# blaster.net
KiCad netlist of a schematic drawn in EAGLE
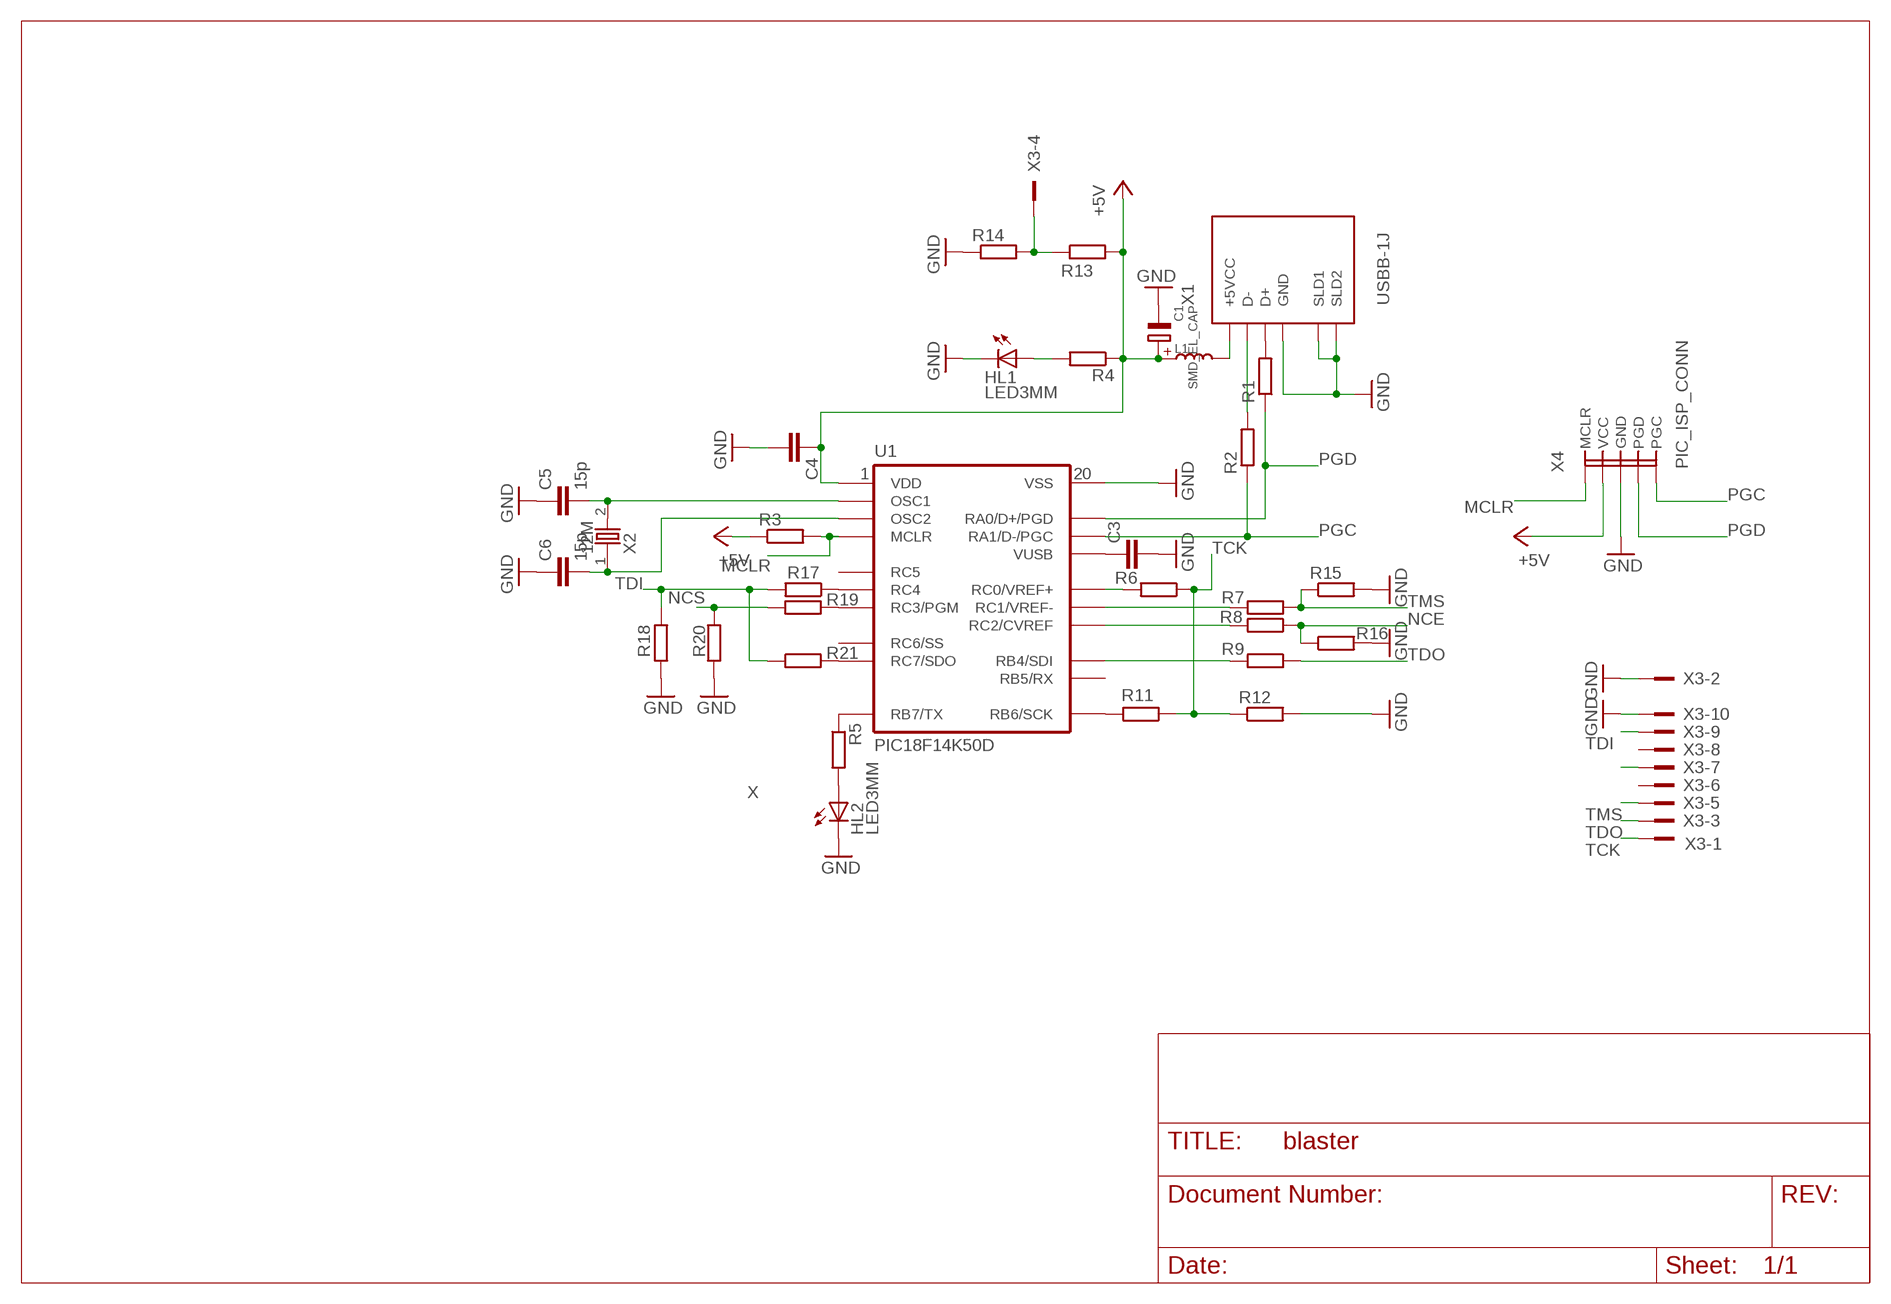
[diagram p0: schematic, sheet 1]

(export (version "E")
  (design (tool "Eeschema 10.0.6"))
  (components
    (comp (ref "C1")
      (value "SMD_EL_CAP")
      (footprint "eagle-import:153CLV-0405")
      (libsource (lib "eagle-import") (part "SMD_EL_CAP"))
    )
    (comp (ref "C3")
      (value "SMD_CAPC1206K")
      (footprint "eagle-import:C1206K")
      (libsource (lib "eagle-import") (part "SMD_CAPC1206K"))
    )
    (comp (ref "C4")
      (value "SMD_CAPC1206K")
      (footprint "eagle-import:C1206K")
      (libsource (lib "eagle-import") (part "SMD_CAPC1206K"))
    )
    (comp (ref "C5")
      (value "15p")
      (footprint "eagle-import:C0805D")
      (libsource (lib "eagle-import") (part "C0805"))
    )
    (comp (ref "C6")
      (value "15p")
      (footprint "eagle-import:C0805D")
      (libsource (lib "eagle-import") (part "C0805"))
    )
    (comp (ref "HL1")
      (value "LED3MM")
      (footprint "eagle-import:LED3MM")
      (libsource (lib "eagle-import") (part "LED3MM"))
    )
    (comp (ref "HL2")
      (value "LED3MM")
      (footprint "eagle-import:LED3MM")
      (libsource (lib "eagle-import") (part "LED3MM"))
    )
    (comp (ref "L1")
      (value "INDUCTORIND2")
      (footprint "eagle-import:INDUCTOR2")
      (libsource (lib "eagle-import") (part "INDUCTORIND2"))
    )
    (comp (ref "R1")
      (value "SMD_RES")
      (footprint "eagle-import:R1206")
      (libsource (lib "eagle-import") (part "SMD_RES"))
    )
    (comp (ref "R2")
      (value "SMD_RES")
      (footprint "eagle-import:R1206")
      (libsource (lib "eagle-import") (part "SMD_RES"))
    )
    (comp (ref "R3")
      (value "10k")
      (footprint "eagle-import:R1206")
      (libsource (lib "eagle-import") (part "SMD_RES"))
    )
    (comp (ref "R4")
      (value "1k")
      (footprint "eagle-import:R1206")
      (libsource (lib "eagle-import") (part "SMD_RES"))
    )
    (comp (ref "R5")
      (value "1k")
      (footprint "eagle-import:R1206")
      (libsource (lib "eagle-import") (part "SMD_RES"))
    )
    (comp (ref "R6")
      (value "100")
      (footprint "eagle-import:R1206")
      (libsource (lib "eagle-import") (part "SMD_RES"))
    )
    (comp (ref "R7")
      (value "100")
      (footprint "eagle-import:R1206")
      (libsource (lib "eagle-import") (part "SMD_RES"))
    )
    (comp (ref "R8")
      (value "100")
      (footprint "eagle-import:R1206")
      (libsource (lib "eagle-import") (part "SMD_RES"))
    )
    (comp (ref "R9")
      (value "100")
      (footprint "eagle-import:R1206")
      (libsource (lib "eagle-import") (part "SMD_RES"))
    )
    (comp (ref "R11")
      (value "100")
      (footprint "eagle-import:R1206")
      (libsource (lib "eagle-import") (part "SMD_RES"))
    )
    (comp (ref "R12")
      (value "200")
      (footprint "eagle-import:R1206")
      (libsource (lib "eagle-import") (part "SMD_RES"))
    )
    (comp (ref "R13")
      (value "100")
      (footprint "eagle-import:R1206")
      (libsource (lib "eagle-import") (part "SMD_RES"))
    )
    (comp (ref "R14")
      (value "200")
      (footprint "eagle-import:R1206")
      (libsource (lib "eagle-import") (part "SMD_RES"))
    )
    (comp (ref "R15")
      (value "200")
      (footprint "eagle-import:R1206")
      (libsource (lib "eagle-import") (part "SMD_RES"))
    )
    (comp (ref "R16")
      (value "200")
      (footprint "eagle-import:R1206")
      (libsource (lib "eagle-import") (part "SMD_RES"))
    )
    (comp (ref "R17")
      (value "100")
      (footprint "eagle-import:R1206")
      (libsource (lib "eagle-import") (part "SMD_RES"))
    )
    (comp (ref "R18")
      (value "200")
      (footprint "eagle-import:R1206")
      (libsource (lib "eagle-import") (part "SMD_RES"))
    )
    (comp (ref "R19")
      (value "100")
      (footprint "eagle-import:R1206")
      (libsource (lib "eagle-import") (part "SMD_RES"))
    )
    (comp (ref "R20")
      (value "200")
      (footprint "eagle-import:R1206")
      (libsource (lib "eagle-import") (part "SMD_RES"))
    )
    (comp (ref "R21")
      (value "100")
      (footprint "eagle-import:R1206")
      (libsource (lib "eagle-import") (part "SMD_RES"))
    )
    (comp (ref "U1")
      (value "PIC18F14K50D")
      (footprint "eagle-import:SO20-DW")
      (libsource (lib "eagle-import") (part "PIC18F14K50D"))
    )
    (comp (ref "X1")
      (value "USBB-1J")
      (footprint "eagle-import:USBB-1J")
      (libsource (lib "eagle-import") (part "USBB-1J"))
    )
    (comp (ref "X2")
      (value "12М")
      (footprint "eagle-import:HC49_S")
      (libsource (lib "eagle-import") (part "HC49/S"))
    )
    (comp (ref "X3")
      (value "X")
      (footprint "eagle-import:PAK100_2500-5-10")
      (fields (field (name "OC_FARNELL") "1788669") (field (name "OC_NEWARK") "unknown"))
      (libsource (lib "eagle-import") (part "DC-10_CON5"))
    )
    (comp (ref "X4")
      (value "PIC_ISP_CONN")
      (footprint "eagle-import:PLC-5PIN")
      (libsource (lib "eagle-import") (part "PIC_ISP_CONN"))
    )
  )
  (nets
    (net (code "1") (name "+5V") (class "Default")
      (node (ref "C1") (pin "+") (pinfunction "P$1_+") (pintype "bidirectional"))
      (node (ref "C4") (pin "1") (pinfunction "1_1") (pintype "passive"))
      (node (ref "L1") (pin "P$1") (pinfunction "P$1_P$1") (pintype "bidirectional"))
      (node (ref "R13") (pin "2") (pinfunction "2_2") (pintype "passive"))
      (node (ref "R3") (pin "1") (pinfunction "1_1") (pintype "passive"))
      (node (ref "R4") (pin "1") (pinfunction "1_1") (pintype "passive"))
      (node (ref "U1") (pin "1.1") (pinfunction "VDD_1.1") (pintype "power_in"))
      (node (ref "X4") (pin "P$2") (pinfunction "VCC_P$2") (pintype "bidirectional"))
    )
    (net (code "2") (name "/MCLR") (class "Default")
      (node (ref "R3") (pin "2") (pinfunction "2_2") (pintype "passive"))
      (node (ref "U1") (pin "1.4") (pinfunction "MCLR_1.4") (pintype "passive"))
      (node (ref "X4") (pin "P$1") (pinfunction "MCLR_P$1") (pintype "bidirectional"))
    )
    (net (code "3") (name "/NCE") (class "Default")
      (node (ref "R16") (pin "1") (pinfunction "1_1") (pintype "passive"))
      (node (ref "R8") (pin "1") (pinfunction "1_1") (pintype "passive"))
    )
    (net (code "4") (name "/NCS") (class "Default")
      (node (ref "R19") (pin "1") (pinfunction "1_1") (pintype "passive"))
      (node (ref "R20") (pin "2") (pinfunction "2_2") (pintype "passive"))
    )
    (net (code "5") (name "/PGC") (class "Default")
      (node (ref "R2") (pin "1") (pinfunction "1_1") (pintype "passive"))
      (node (ref "U1") (pin "1.18") (pinfunction "RA1/D-/PGC_1.18") (pintype "power_in"))
      (node (ref "X4") (pin "P$5") (pinfunction "PGC_P$5") (pintype "bidirectional"))
    )
    (net (code "6") (name "/PGD") (class "Default")
      (node (ref "R1") (pin "1") (pinfunction "1_1") (pintype "passive"))
      (node (ref "U1") (pin "1.19") (pinfunction "RA0/D+/PGD_1.19") (pintype "power_in"))
      (node (ref "X4") (pin "P$4") (pinfunction "PGD_P$4") (pintype "bidirectional"))
    )
    (net (code "7") (name "/TCK") (class "Default")
      (node (ref "R11") (pin "1") (pinfunction "1_1") (pintype "passive"))
      (node (ref "R12") (pin "1") (pinfunction "1_1") (pintype "passive"))
      (node (ref "R6") (pin "1") (pinfunction "1_1") (pintype "passive"))
      (node (ref "X3") (pin "1") (pinfunction "KL_1") (pintype "passive"))
    )
    (net (code "8") (name "/TDI") (class "Default")
      (node (ref "R17") (pin "2") (pinfunction "2_2") (pintype "passive"))
      (node (ref "R18") (pin "2") (pinfunction "2_2") (pintype "passive"))
      (node (ref "R21") (pin "1") (pinfunction "1_1") (pintype "passive"))
      (node (ref "X3") (pin "9") (pinfunction "KL_9") (pintype "passive"))
    )
    (net (code "9") (name "/TDO") (class "Default")
      (node (ref "R9") (pin "1") (pinfunction "1_1") (pintype "passive"))
      (node (ref "X3") (pin "3") (pinfunction "KL_3") (pintype "passive"))
    )
    (net (code "10") (name "/TMS") (class "Default")
      (node (ref "R15") (pin "1") (pinfunction "1_1") (pintype "passive"))
      (node (ref "R7") (pin "1") (pinfunction "1_1") (pintype "passive"))
      (node (ref "X3") (pin "5") (pinfunction "KL_5") (pintype "passive"))
    )
    (net (code "11") (name "GND") (class "Default")
      (node (ref "C1") (pin "-") (pinfunction "P$2_-") (pintype "bidirectional"))
      (node (ref "C3") (pin "2") (pinfunction "2_2") (pintype "passive"))
      (node (ref "C4") (pin "2") (pinfunction "2_2") (pintype "passive"))
      (node (ref "C5") (pin "1") (pinfunction "1_1") (pintype "passive"))
      (node (ref "C6") (pin "1") (pinfunction "1_1") (pintype "passive"))
      (node (ref "HL1") (pin "K") (pinfunction "C_K") (pintype "passive"))
      (node (ref "HL2") (pin "K") (pinfunction "C_K") (pintype "passive"))
      (node (ref "R12") (pin "2") (pinfunction "2_2") (pintype "passive"))
      (node (ref "R14") (pin "1") (pinfunction "1_1") (pintype "passive"))
      (node (ref "R15") (pin "2") (pinfunction "2_2") (pintype "passive"))
      (node (ref "R16") (pin "2") (pinfunction "2_2") (pintype "passive"))
      (node (ref "R18") (pin "1") (pinfunction "1_1") (pintype "passive"))
      (node (ref "R20") (pin "1") (pinfunction "1_1") (pintype "passive"))
      (node (ref "U1") (pin "1.20") (pinfunction "VSS_1.20") (pintype "power_in"))
      (node (ref "X1") (pin "4") (pinfunction "GND_4") (pintype "bidirectional"))
      (node (ref "X1") (pin "5") (pinfunction "SLD1_5") (pintype "bidirectional"))
      (node (ref "X1") (pin "6") (pinfunction "SLD2_6") (pintype "bidirectional"))
      (node (ref "X3") (pin "10") (pinfunction "KL_10") (pintype "passive"))
      (node (ref "X3") (pin "2") (pinfunction "KL_2") (pintype "passive"))
      (node (ref "X4") (pin "P$3") (pinfunction "GND_P$3") (pintype "bidirectional"))
    )
    (net (code "12") (name "Net-(HL1-PadA)") (class "Default")
      (node (ref "HL1") (pin "A") (pinfunction "A_A") (pintype "passive"))
      (node (ref "R4") (pin "2") (pinfunction "2_2") (pintype "passive"))
    )
    (net (code "13") (name "Net-(HL2-PadA)") (class "Default")
      (node (ref "HL2") (pin "A") (pinfunction "A_A") (pintype "passive"))
      (node (ref "R5") (pin "2") (pinfunction "2_2") (pintype "passive"))
    )
    (net (code "14") (name "Net-(U1-OSC1)") (class "Default")
      (node (ref "C5") (pin "2") (pinfunction "2_2") (pintype "passive"))
      (node (ref "U1") (pin "1.2") (pinfunction "OSC1_1.2") (pintype "power_in"))
      (node (ref "X2") (pin "2") (pinfunction "2_2") (pintype "passive"))
    )
    (net (code "15") (name "Net-(U1-OSC2)") (class "Default")
      (node (ref "C6") (pin "2") (pinfunction "2_2") (pintype "passive"))
      (node (ref "U1") (pin "1.3") (pinfunction "OSC2_1.3") (pintype "passive"))
      (node (ref "X2") (pin "1") (pinfunction "1_1") (pintype "passive"))
    )
    (net (code "16") (name "Net-(U1-RB4{slash}SDI)") (class "Default")
      (node (ref "R9") (pin "2") (pinfunction "2_2") (pintype "passive"))
      (node (ref "U1") (pin "1.13") (pinfunction "RB4/SDI_1.13") (pintype "output"))
    )
    (net (code "17") (name "Net-(U1-RB6{slash}SCK)") (class "Default")
      (node (ref "R11") (pin "2") (pinfunction "2_2") (pintype "passive"))
      (node (ref "U1") (pin "1.11") (pinfunction "RB6/SCK_1.11") (pintype "power_in"))
    )
    (net (code "18") (name "Net-(U1-RB7{slash}TX)") (class "Default")
      (node (ref "R5") (pin "1") (pinfunction "1_1") (pintype "passive"))
      (node (ref "U1") (pin "1.10") (pinfunction "RB7/TX_1.10") (pintype "bidirectional"))
    )
    (net (code "19") (name "Net-(U1-RC0{slash}VREF+)") (class "Default")
      (node (ref "R6") (pin "2") (pinfunction "2_2") (pintype "passive"))
      (node (ref "U1") (pin "1.16") (pinfunction "RC0/VREF+_1.16") (pintype "output"))
    )
    (net (code "20") (name "Net-(U1-RC1{slash}VREF-)") (class "Default")
      (node (ref "R7") (pin "2") (pinfunction "2_2") (pintype "passive"))
      (node (ref "U1") (pin "1.15") (pinfunction "RC1/VREF-_1.15") (pintype "output"))
    )
    (net (code "21") (name "Net-(U1-RC2{slash}CVREF)") (class "Default")
      (node (ref "R8") (pin "2") (pinfunction "2_2") (pintype "passive"))
      (node (ref "U1") (pin "1.14") (pinfunction "RC2/CVREF_1.14") (pintype "power_in"))
    )
    (net (code "22") (name "Net-(U1-RC3{slash}PGM)") (class "Default")
      (node (ref "R19") (pin "2") (pinfunction "2_2") (pintype "passive"))
      (node (ref "U1") (pin "1.7") (pinfunction "RC3/PGM_1.7") (pintype "bidirectional"))
    )
    (net (code "23") (name "Net-(U1-RC4)") (class "Default")
      (node (ref "R17") (pin "1") (pinfunction "1_1") (pintype "passive"))
      (node (ref "U1") (pin "1.6") (pinfunction "RC4_1.6") (pintype "input"))
    )
    (net (code "24") (name "Net-(U1-RC7{slash}SDO)") (class "Default")
      (node (ref "R21") (pin "2") (pinfunction "2_2") (pintype "passive"))
      (node (ref "U1") (pin "1.9") (pinfunction "RC7/SDO_1.9") (pintype "input"))
    )
    (net (code "25") (name "Net-(U1-VUSB)") (class "Default")
      (node (ref "C3") (pin "1") (pinfunction "1_1") (pintype "passive"))
      (node (ref "U1") (pin "1.17") (pinfunction "VUSB_1.17") (pintype "power_in"))
    )
    (net (code "26") (name "Net-(X1-+5VCC)") (class "Default")
      (node (ref "L1") (pin "P$2") (pinfunction "P$2_P$2") (pintype "bidirectional"))
      (node (ref "X1") (pin "1") (pinfunction "+5VCC_1") (pintype "bidirectional"))
    )
    (net (code "27") (name "Net-(X1-D+)") (class "Default")
      (node (ref "R1") (pin "2") (pinfunction "2_2") (pintype "passive"))
      (node (ref "X1") (pin "3") (pinfunction "D+_3") (pintype "bidirectional"))
    )
    (net (code "28") (name "Net-(X1-D-)") (class "Default")
      (node (ref "R2") (pin "2") (pinfunction "2_2") (pintype "passive"))
      (node (ref "X1") (pin "2") (pinfunction "D-_2") (pintype "bidirectional"))
    )
    (net (code "29") (name "Net-(X3E-KL)") (class "Default")
      (node (ref "R13") (pin "1") (pinfunction "1_1") (pintype "passive"))
      (node (ref "R14") (pin "2") (pinfunction "2_2") (pintype "passive"))
      (node (ref "X3") (pin "4") (pinfunction "KL_4") (pintype "passive"))
    )
    (net (code "30") (name "unconnected-(U1-RB5{slash}RX-Pad1.12)") (class "Default")
      (node (ref "U1") (pin "1.12") (pinfunction "RB5/RX_1.12") (pintype "output"))
    )
    (net (code "31") (name "unconnected-(U1-RC5-Pad1.5)") (class "Default")
      (node (ref "U1") (pin "1.5") (pinfunction "RC5_1.5") (pintype "input"))
    )
    (net (code "32") (name "unconnected-(U1-RC6{slash}SS-Pad1.8)") (class "Default")
      (node (ref "U1") (pin "1.8") (pinfunction "RC6/SS_1.8") (pintype "input"))
    )
    (net (code "33") (name "unconnected-(X3G-KL-Pad6)") (class "Default")
      (node (ref "X3") (pin "6") (pinfunction "KL_6") (pintype "passive"))
    )
    (net (code "34") (name "unconnected-(X3H-KL-Pad7)") (class "Default")
      (node (ref "X3") (pin "7") (pinfunction "KL_7") (pintype "passive"))
    )
    (net (code "35") (name "unconnected-(X3I-KL-Pad8)") (class "Default")
      (node (ref "X3") (pin "8") (pinfunction "KL_8") (pintype "passive"))
    )
  )
)
